# 261105902xxxx-HW-V2_1.net
KiCad netlist of a schematic drawn in EAGLE
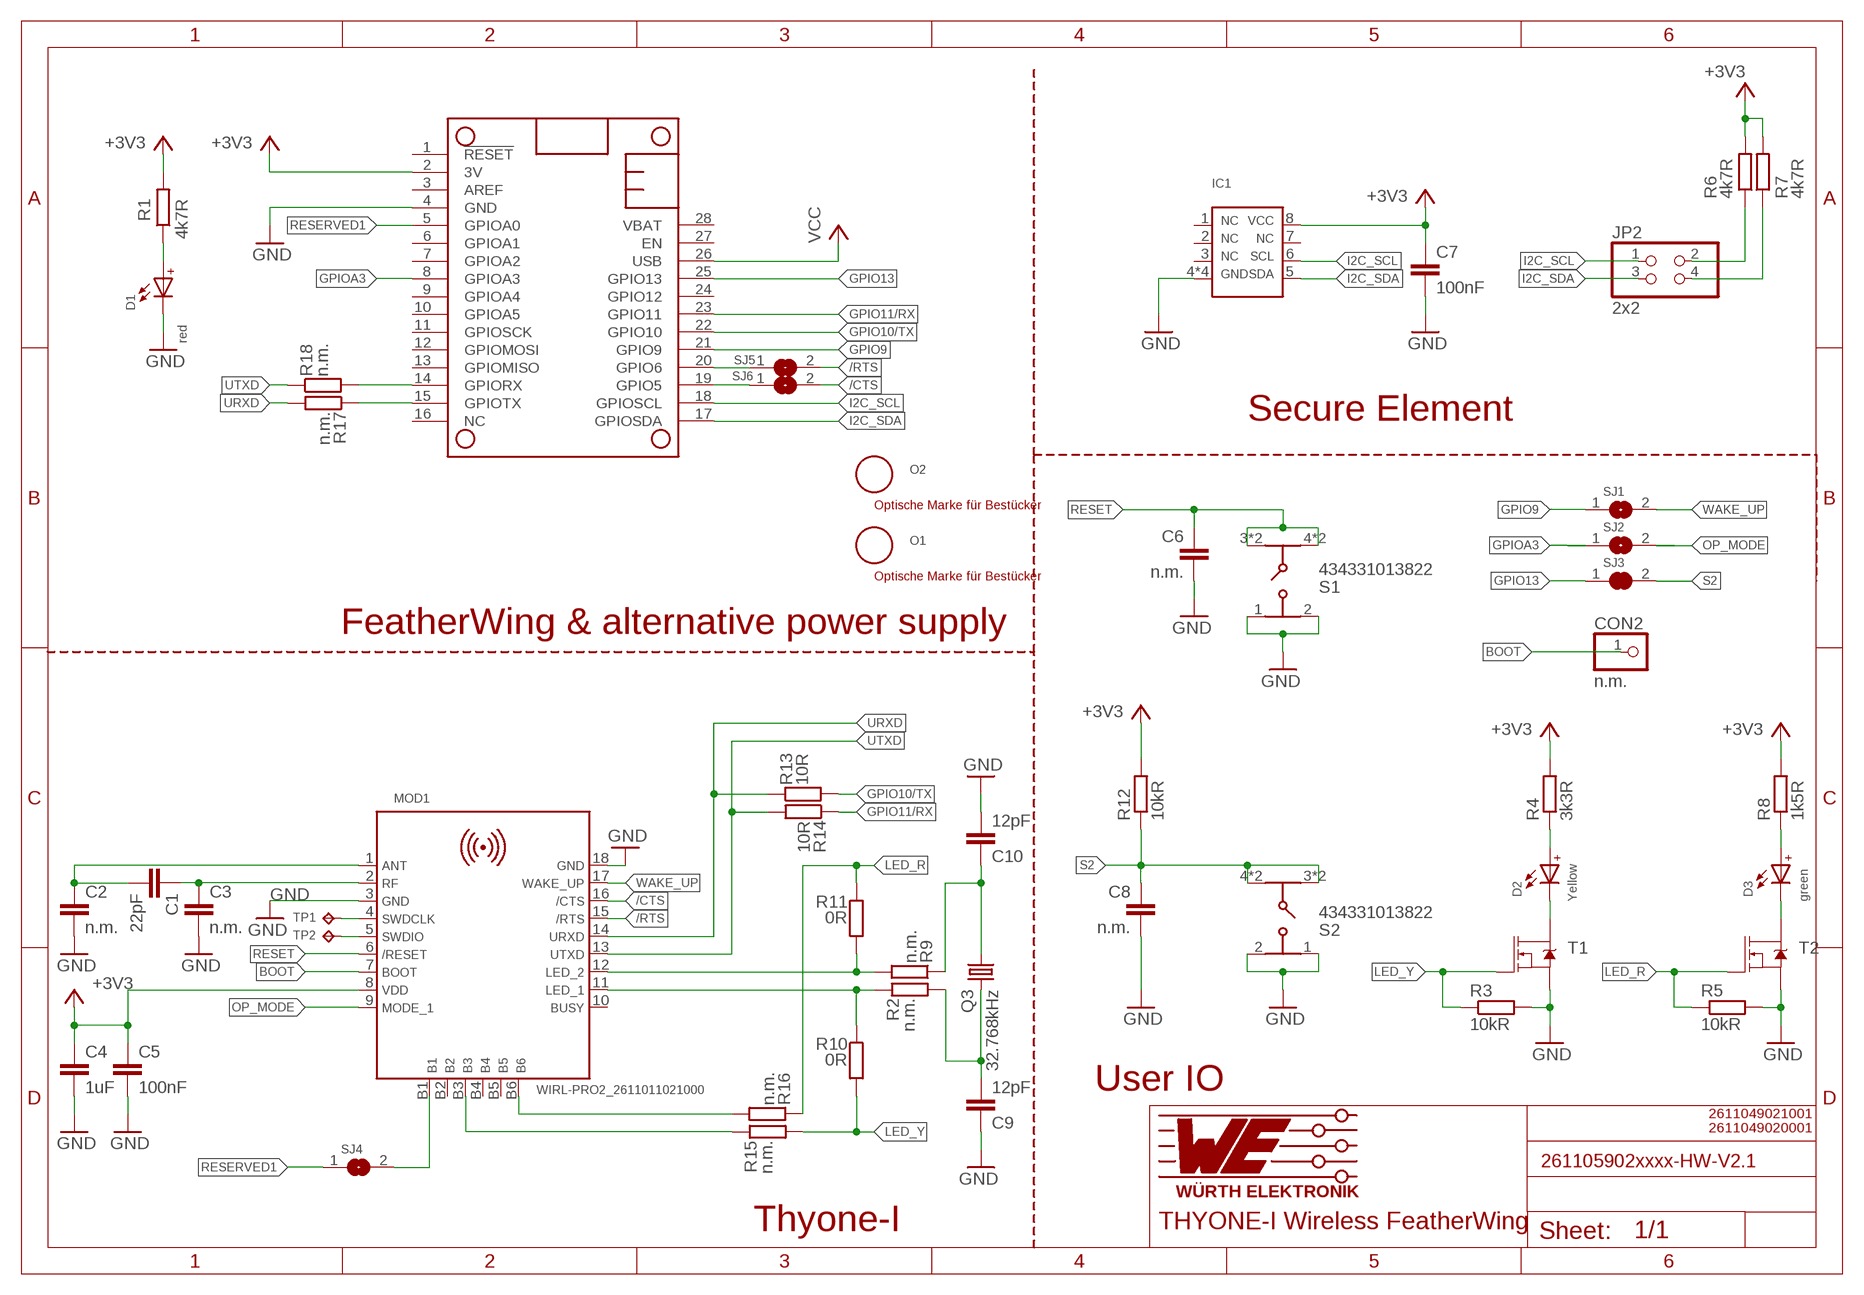
[diagram p0: schematic, sheet 1]

(export (version "E")
  (design (tool "Eeschema 10.0.6"))
  (components
    (comp (ref "C1")
      (value "22pF")
      (footprint "eagle-import:C0402_IPC")
      (fields (field (name "MANUFACTURER") "Samsung"))
      (libsource (lib "eagle-import") (part "rcl-amber_C0402_IPC22PF"))
    )
    (comp (ref "C2")
      (value "n.m.")
      (footprint "eagle-import:C0402_IPC")
      (fields (field (name "MANUFACTURER") "Würth Elektronik"))
      (libsource (lib "eagle-import") (part "C0402_IPC"))
    )
    (comp (ref "C3")
      (value "n.m.")
      (footprint "eagle-import:C0402_IPC")
      (fields (field (name "MANUFACTURER") "Würth Elektronik"))
      (libsource (lib "eagle-import") (part "C0402_IPC"))
    )
    (comp (ref "C4")
      (value "1uF")
      (footprint "eagle-import:C0402_IPC")
      (fields (field (name "MANUFACTURER") "Samsung"))
      (libsource (lib "eagle-import") (part "rcl-amber_C0402_IPC1UF"))
    )
    (comp (ref "C5")
      (value "100nF")
      (footprint "eagle-import:C0402_IPC")
      (fields (field (name "MANUFACTURER") "Yageo"))
      (libsource (lib "eagle-import") (part "rcl-amber_C0402_IPC100NF"))
    )
    (comp (ref "C6")
      (value "n.m.")
      (footprint "eagle-import:C0402_IPC")
      (fields (field (name "MANUFACTURER") "Würth Elektronik"))
      (libsource (lib "eagle-import") (part "C0402_IPC"))
    )
    (comp (ref "C7")
      (value "100nF")
      (footprint "eagle-import:C0402_IPC")
      (fields (field (name "MANUFACTURER") "Yageo"))
      (libsource (lib "eagle-import") (part "rcl-amber_C0402_IPC100NF"))
    )
    (comp (ref "C8")
      (value "n.m.")
      (footprint "eagle-import:C0402_IPC")
      (fields (field (name "MANUFACTURER") "Würth Elektronik"))
      (libsource (lib "eagle-import") (part "C0402_IPC"))
    )
    (comp (ref "C9")
      (value "12pF")
      (footprint "eagle-import:C0402_IPC")
      (fields (field (name "MANUFACTURER") "Yageo"))
      (libsource (lib "eagle-import") (part "C0402_IPC12PF"))
    )
    (comp (ref "C10")
      (value "12pF")
      (footprint "eagle-import:C0402_IPC")
      (fields (field (name "MANUFACTURER") "Yageo"))
      (libsource (lib "eagle-import") (part "C0402_IPC12PF"))
    )
    (comp (ref "CON2")
      (value "n.m.")
      (footprint "eagle-import:1X01_R")
      (libsource (lib "eagle-import") (part "PINHD-1X1/R"))
    )
    (comp (ref "D1")
      (value "red")
      (footprint "eagle-import:WL-SMSW_1204_A")
      (fields (field (name "MANUFACTURER") "Würth Elektronik"))
      (libsource (lib "eagle-import") (part "WL-SMSW_1204_155124VS73200"))
    )
    (comp (ref "D2")
      (value "Yellow")
      (footprint "eagle-import:WL-SMSW_1204_A")
      (fields (field (name "MANUFACTURER") "Würth Elektronik"))
      (libsource (lib "eagle-import") (part "WL-SMSW_1204_155124YS73200"))
    )
    (comp (ref "D3")
      (value "green")
      (footprint "eagle-import:WL-SMSW_1204_A")
      (fields (field (name "MANUFACTURER") "Würth Elektronik"))
      (libsource (lib "eagle-import") (part "WL-SMSW_1204_155124VS73200"))
    )
    (comp (ref "IC1")
      (value "ATECC608B")
      (footprint "eagle-import:UDFN-8")
      (fields (field (name "MANUFACTURER") "Microchip") (field (name "MANUFACTURER_1") "microchip"))
      (libsource (lib "eagle-import") (part "ATECC608B-TNGTLS"))
    )
    (comp (ref "JP2")
      (value "2x2")
      (footprint "eagle-import:2X02")
      (fields (field (name "MANUFACTURER") "Würth Elektronik"))
      (libsource (lib "eagle-import") (part "PINHD-2X2"))
    )
    (comp (ref "MOD1")
      (value "WIRL-PRO2_2611011021000")
      (footprint "eagle-import:WIRL-PRO2_2611011021000")
      (fields (field (name "MANUFACTURER") "Würth Elektronik"))
      (libsource (lib "eagle-import") (part "WIRL-PRO2_2611011021000"))
    )
    (comp (ref "MS1")
      (value "header: 1 x 12 & 1 x 16")
      (footprint "eagle-import:FEATHERWING")
      (fields (field (name "COMMENT") "Kit containing 2 headers") (field (name "MANUFACTURER") "Adafruit"))
      (libsource (lib "eagle-import") (part "FEATHERWING"))
    )
    (comp (ref "O1")
      (value "n.m.")
      (footprint "eagle-import:OPTISCHE_MARKE")
      (libsource (lib "eagle-import") (part "OPT_MARKE"))
    )
    (comp (ref "O2")
      (value "n.m.")
      (footprint "eagle-import:OPTISCHE_MARKE")
      (libsource (lib "eagle-import") (part "OPT_MARKE"))
    )
    (comp (ref "Q3")
      (value "32.768kHz")
      (footprint "eagle-import:3216")
      (fields
        (field (name "MANUFACTURER") "Microcrystal")
        (field (name "MANUFACTURER_1") "Würth Elektronik")
        (field (name "MANUFACTURER_2") "Microcrystal")
        (field (name "NR") "830009706")
        (field (name "NR_2") "CM7V-T1A-32.768k-9pF-20PPM-TA-QA T3")
      )
      (libsource (lib "eagle-import") (part "3216"))
    )
    (comp (ref "R1")
      (value "4k7R")
      (footprint "eagle-import:R0402_IPC")
      (fields (field (name "MANUFACTURER") "Yageo"))
      (libsource (lib "eagle-import") (part "R0402_IPC4K7"))
    )
    (comp (ref "R2")
      (value "n.m.")
      (footprint "eagle-import:R0402_IPC")
      (fields (field (name "MANUFACTURER") "Yageo"))
      (libsource (lib "eagle-import") (part "R0402_IPC"))
    )
    (comp (ref "R3")
      (value "10kR")
      (footprint "eagle-import:R0402_IPC")
      (fields (field (name "MANUFACTURER") "Yageo"))
      (libsource (lib "eagle-import") (part "R0402_IPC10KR"))
    )
    (comp (ref "R4")
      (value "3k3R")
      (footprint "eagle-import:R0402_IPC")
      (fields (field (name "MANUFACTURER") "Yageo"))
      (libsource (lib "eagle-import") (part "R0402_IPC3K3R"))
    )
    (comp (ref "R5")
      (value "10kR")
      (footprint "eagle-import:R0402_IPC")
      (fields (field (name "MANUFACTURER") "Yageo"))
      (libsource (lib "eagle-import") (part "R0402_IPC10KR"))
    )
    (comp (ref "R6")
      (value "4k7R")
      (footprint "eagle-import:R0402_IPC")
      (fields (field (name "MANUFACTURER") "Yageo"))
      (libsource (lib "eagle-import") (part "R0402_IPC4K7"))
    )
    (comp (ref "R7")
      (value "4k7R")
      (footprint "eagle-import:R0402_IPC")
      (fields (field (name "MANUFACTURER") "Yageo"))
      (libsource (lib "eagle-import") (part "R0402_IPC4K7"))
    )
    (comp (ref "R8")
      (value "1k5R")
      (footprint "eagle-import:R0402_IPC")
      (fields (field (name "MANUFACTURER") "Yageo"))
      (libsource (lib "eagle-import") (part "R0402_IPC1K5R"))
    )
    (comp (ref "R9")
      (value "n.m.")
      (footprint "eagle-import:R0402_IPC")
      (fields (field (name "MANUFACTURER") "Yageo"))
      (libsource (lib "eagle-import") (part "R0402_IPC"))
    )
    (comp (ref "R10")
      (value "0R")
      (footprint "eagle-import:R0402_IPC")
      (fields (field (name "MANUFACTURER") "Yageo"))
      (libsource (lib "eagle-import") (part "R0402_IPC0R"))
    )
    (comp (ref "R11")
      (value "0R")
      (footprint "eagle-import:R0402_IPC")
      (fields (field (name "MANUFACTURER") "Yageo"))
      (libsource (lib "eagle-import") (part "R0402_IPC0R"))
    )
    (comp (ref "R12")
      (value "10kR")
      (footprint "eagle-import:R0402_IPC")
      (fields (field (name "MANUFACTURER") "Yageo"))
      (libsource (lib "eagle-import") (part "R0402_IPC10KR"))
    )
    (comp (ref "R13")
      (value "10R")
      (footprint "eagle-import:R0402_IPC")
      (fields (field (name "MANUFACTURER") "Yageo"))
      (libsource (lib "eagle-import") (part "R0402_IPC10R"))
    )
    (comp (ref "R14")
      (value "10R")
      (footprint "eagle-import:R0402_IPC")
      (fields (field (name "MANUFACTURER") "Yageo"))
      (libsource (lib "eagle-import") (part "R0402_IPC10R"))
    )
    (comp (ref "R15")
      (value "n.m.")
      (footprint "eagle-import:R0402_IPC")
      (fields (field (name "MANUFACTURER") "Yageo"))
      (libsource (lib "eagle-import") (part "R0402_IPC"))
    )
    (comp (ref "R16")
      (value "n.m.")
      (footprint "eagle-import:R0402_IPC")
      (fields (field (name "MANUFACTURER") "Yageo"))
      (libsource (lib "eagle-import") (part "R0402_IPC"))
    )
    (comp (ref "R17")
      (value "n.m.")
      (footprint "eagle-import:R0402_IPC")
      (fields (field (name "MANUFACTURER") "Yageo"))
      (libsource (lib "eagle-import") (part "R0402_IPC"))
    )
    (comp (ref "R18")
      (value "n.m.")
      (footprint "eagle-import:R0402_IPC")
      (fields (field (name "MANUFACTURER") "Yageo"))
      (libsource (lib "eagle-import") (part "R0402_IPC"))
    )
    (comp (ref "S1")
      (value "434331013822")
      (footprint "eagle-import:434331013822")
      (fields (field (name "MANUFACTURER") "Würth Elektronik"))
      (libsource (lib "eagle-import") (part "434331013822"))
    )
    (comp (ref "S2")
      (value "434331013822")
      (footprint "eagle-import:434331013822")
      (fields (field (name "MANUFACTURER") "Würth Elektronik"))
      (libsource (lib "eagle-import") (part "434331013822"))
    )
    (comp (ref "SJ1") (value "SJ") (footprint "eagle-import:SJ") (libsource (lib "eagle-import") (part "SJ")))
    (comp (ref "SJ2") (value "SJ") (footprint "eagle-import:SJ") (libsource (lib "eagle-import") (part "SJ")))
    (comp (ref "SJ3")
      (value "SJ_SHUNTD")
      (footprint "eagle-import:SJ_D")
      (libsource (lib "eagle-import") (part "SJ_SHUNTD"))
    )
    (comp (ref "SJ4") (value "SJ") (footprint "eagle-import:SJ") (libsource (lib "eagle-import") (part "SJ")))
    (comp (ref "SJ5") (value "SJ") (footprint "eagle-import:SJ") (libsource (lib "eagle-import") (part "SJ")))
    (comp (ref "SJ6") (value "SJ") (footprint "eagle-import:SJ") (libsource (lib "eagle-import") (part "SJ")))
    (comp (ref "T1")
      (value "MOSFET-NCH-BSS138")
      (footprint "eagle-import:SOT23-3")
      (fields (field (name "COMMENT") "220mA/50V/3.5O") (field (name "MANUFACTURER") "Diodes Incorporated"))
      (libsource (lib "eagle-import") (part "MOSFET-NCH-BSS138"))
    )
    (comp (ref "T2")
      (value "MOSFET-NCH-BSS138")
      (footprint "eagle-import:SOT23-3")
      (fields (field (name "COMMENT") "220mA/50V/3.5O") (field (name "MANUFACTURER") "Diodes Incorporated"))
      (libsource (lib "eagle-import") (part "MOSFET-NCH-BSS138"))
    )
    (comp (ref "TP1")
      (value "TP15R")
      (footprint "eagle-import:TP15R")
      (libsource (lib "eagle-import") (part "TP15R"))
    )
    (comp (ref "TP2")
      (value "TP15R")
      (footprint "eagle-import:TP15R")
      (libsource (lib "eagle-import") (part "TP15R"))
    )
  )
  (nets
    (net (code "1") (name "+3V3") (class "Default")
      (node (ref "C4") (pin "1") (pinfunction "1_1") (pintype "passive"))
      (node (ref "C5") (pin "1") (pinfunction "1_1") (pintype "passive"))
      (node (ref "C7") (pin "1") (pinfunction "1_1") (pintype "passive"))
      (node (ref "IC1") (pin "8") (pinfunction "VCC_8") (pintype "power_in"))
      (node (ref "MOD1") (pin "8") (pinfunction "VDD_8") (pintype "bidirectional"))
      (node (ref "MS1") (pin "2") (pinfunction "3V_2") (pintype "power_in"))
      (node (ref "R1") (pin "2") (pinfunction "2_2") (pintype "passive"))
      (node (ref "R12") (pin "2") (pinfunction "2_2") (pintype "passive"))
      (node (ref "R4") (pin "2") (pinfunction "2_2") (pintype "passive"))
      (node (ref "R6") (pin "2") (pinfunction "2_2") (pintype "passive"))
      (node (ref "R7") (pin "2") (pinfunction "2_2") (pintype "passive"))
      (node (ref "R8") (pin "2") (pinfunction "2_2") (pintype "passive"))
    )
    (net (code "2") (name "/VBAT") (class "Default")
      (node (ref "MS1") (pin "28") (pinfunction "VBAT_28") (pintype "power_in"))
    )
    (net (code "3") (name "BOOT") (class "Default")
      (node (ref "CON2") (pin "1") (pinfunction "1_1") (pintype "passive"))
      (node (ref "MOD1") (pin "7") (pinfunction "P0.02/BOOT_7") (pintype "bidirectional"))
    )
    (net (code "4") (name "GND") (class "Default")
      (node (ref "C10") (pin "2") (pinfunction "2_2") (pintype "passive"))
      (node (ref "C2") (pin "2") (pinfunction "2_2") (pintype "passive"))
      (node (ref "C3") (pin "2") (pinfunction "2_2") (pintype "passive"))
      (node (ref "C4") (pin "2") (pinfunction "2_2") (pintype "passive"))
      (node (ref "C5") (pin "2") (pinfunction "2_2") (pintype "passive"))
      (node (ref "C6") (pin "2") (pinfunction "2_2") (pintype "passive"))
      (node (ref "C7") (pin "2") (pinfunction "2_2") (pintype "passive"))
      (node (ref "C8") (pin "2") (pinfunction "2_2") (pintype "passive"))
      (node (ref "C9") (pin "1") (pinfunction "1_1") (pintype "passive"))
      (node (ref "D1") (pin "1") (pinfunction "-_1") (pintype "passive"))
      (node (ref "IC1") (pin "4") (pinfunction "GND_4") (pintype "power_in"))
      (node (ref "IC1") (pin "P$1") (pinfunction "GND_P$1") (pintype "power_in"))
      (node (ref "IC1") (pin "P$2") (pinfunction "GND_P$2") (pintype "power_in"))
      (node (ref "IC1") (pin "THERMAL_PAD") (pinfunction "GND_THERMAL_PAD") (pintype "power_in"))
      (node (ref "MOD1") (pin "18") (pinfunction "GND_18") (pintype "bidirectional"))
      (node (ref "MOD1") (pin "3") (pinfunction "GND_3") (pintype "bidirectional"))
      (node (ref "MS1") (pin "4") (pinfunction "GND_4") (pintype "power_in"))
      (node (ref "R3") (pin "2") (pinfunction "2_2") (pintype "passive"))
      (node (ref "R5") (pin "2") (pinfunction "2_2") (pintype "passive"))
      (node (ref "S1") (pin "1") (pinfunction "1_1") (pintype "passive"))
      (node (ref "S1") (pin "2") (pinfunction "2_2") (pintype "passive"))
      (node (ref "S2") (pin "1") (pinfunction "1_1") (pintype "passive"))
      (node (ref "S2") (pin "2") (pinfunction "2_2") (pintype "passive"))
      (node (ref "T1") (pin "2") (pinfunction "S_2") (pintype "bidirectional"))
      (node (ref "T2") (pin "2") (pinfunction "S_2") (pintype "bidirectional"))
    )
    (net (code "5") (name "GPIO9") (class "Default")
      (node (ref "MS1") (pin "21") (pinfunction "GPIO9_21") (pintype "bidirectional"))
      (node (ref "SJ1") (pin "1") (pinfunction "1_1") (pintype "passive"))
    )
    (net (code "6") (name "GPIO10{slash}TX") (class "Default")
      (node (ref "MS1") (pin "22") (pinfunction "GPIO10_22") (pintype "bidirectional"))
      (node (ref "R13") (pin "2") (pinfunction "2_2") (pintype "passive"))
    )
    (net (code "7") (name "GPIO11{slash}RX") (class "Default")
      (node (ref "MS1") (pin "23") (pinfunction "GPIO11_23") (pintype "bidirectional"))
      (node (ref "R14") (pin "1") (pinfunction "1_1") (pintype "passive"))
    )
    (net (code "8") (name "GPIO13") (class "Default")
      (node (ref "MS1") (pin "25") (pinfunction "GPIO13_25") (pintype "bidirectional"))
      (node (ref "SJ3") (pin "1") (pinfunction "1_1") (pintype "passive"))
    )
    (net (code "9") (name "GPIOA3") (class "Default")
      (node (ref "MS1") (pin "8") (pinfunction "GPIOA3_8") (pintype "bidirectional"))
      (node (ref "SJ2") (pin "1") (pinfunction "1_1") (pintype "passive"))
    )
    (net (code "10") (name "I2C_SCL") (class "Default")
      (node (ref "IC1") (pin "6") (pinfunction "SCL_6") (pintype "bidirectional"))
      (node (ref "JP2") (pin "1") (pinfunction "1_1") (pintype "passive"))
      (node (ref "MS1") (pin "18") (pinfunction "GPIOSCL_18") (pintype "bidirectional"))
    )
    (net (code "11") (name "I2C_SDA") (class "Default")
      (node (ref "IC1") (pin "5") (pinfunction "SDA_5") (pintype "bidirectional"))
      (node (ref "JP2") (pin "3") (pinfunction "3_3") (pintype "passive"))
      (node (ref "MS1") (pin "17") (pinfunction "GPIOSDA_17") (pintype "bidirectional"))
    )
    (net (code "12") (name "LED_R") (class "Default")
      (node (ref "R11") (pin "1") (pinfunction "1_1") (pintype "passive"))
      (node (ref "R16") (pin "1") (pinfunction "1_1") (pintype "passive"))
      (node (ref "R5") (pin "1") (pinfunction "1_1") (pintype "passive"))
      (node (ref "T2") (pin "1") (pinfunction "G_1") (pintype "bidirectional"))
    )
    (net (code "13") (name "LED_Y") (class "Default")
      (node (ref "R10") (pin "2") (pinfunction "2_2") (pintype "passive"))
      (node (ref "R15") (pin "2") (pinfunction "2_2") (pintype "passive"))
      (node (ref "R3") (pin "1") (pinfunction "1_1") (pintype "passive"))
      (node (ref "T1") (pin "1") (pinfunction "G_1") (pintype "bidirectional"))
    )
    (net (code "14") (name "Net-(C9-Pad2)") (class "Default")
      (node (ref "C9") (pin "2") (pinfunction "2_2") (pintype "passive"))
      (node (ref "Q3") (pin "2") (pinfunction "2_2") (pintype "passive"))
      (node (ref "R2") (pin "2") (pinfunction "2_2") (pintype "passive"))
    )
    (net (code "15") (name "Net-(C10-Pad1)") (class "Default")
      (node (ref "C10") (pin "1") (pinfunction "1_1") (pintype "passive"))
      (node (ref "Q3") (pin "1") (pinfunction "1_1") (pintype "passive"))
      (node (ref "R9") (pin "1") (pinfunction "1_1") (pintype "passive"))
    )
    (net (code "16") (name "Net-(D1-+)") (class "Default")
      (node (ref "D1") (pin "2") (pinfunction "+_2") (pintype "passive"))
      (node (ref "R1") (pin "1") (pinfunction "1_1") (pintype "passive"))
    )
    (net (code "17") (name "Net-(D2-+)") (class "Default")
      (node (ref "D2") (pin "2") (pinfunction "+_2") (pintype "passive"))
      (node (ref "R4") (pin "1") (pinfunction "1_1") (pintype "passive"))
    )
    (net (code "18") (name "Net-(D2--)") (class "Default")
      (node (ref "D2") (pin "1") (pinfunction "-_1") (pintype "passive"))
      (node (ref "T1") (pin "3") (pinfunction "D_3") (pintype "bidirectional"))
    )
    (net (code "19") (name "Net-(D3-+)") (class "Default")
      (node (ref "D3") (pin "2") (pinfunction "+_2") (pintype "passive"))
      (node (ref "R8") (pin "1") (pinfunction "1_1") (pintype "passive"))
    )
    (net (code "20") (name "Net-(D3--)") (class "Default")
      (node (ref "D3") (pin "1") (pinfunction "-_1") (pintype "passive"))
      (node (ref "T2") (pin "3") (pinfunction "D_3") (pintype "bidirectional"))
    )
    (net (code "21") (name "Net-(JP2-Pad2)") (class "Default")
      (node (ref "JP2") (pin "2") (pinfunction "2_2") (pintype "passive"))
      (node (ref "R6") (pin "1") (pinfunction "1_1") (pintype "passive"))
    )
    (net (code "22") (name "Net-(JP2-Pad4)") (class "Default")
      (node (ref "JP2") (pin "4") (pinfunction "4_4") (pintype "passive"))
      (node (ref "R7") (pin "1") (pinfunction "1_1") (pintype "passive"))
    )
    (net (code "23") (name "Net-(MOD1-ANT_PAD)") (class "Default")
      (node (ref "C1") (pin "2") (pinfunction "2_2") (pintype "passive"))
      (node (ref "C2") (pin "1") (pinfunction "1_1") (pintype "passive"))
      (node (ref "MOD1") (pin "1") (pinfunction "ANT_PAD_1") (pintype "bidirectional"))
    )
    (net (code "24") (name "Net-(MOD1-P0.00{slash}LED_1)") (class "Default")
      (node (ref "MOD1") (pin "11") (pinfunction "P0.00/LED_1_11") (pintype "bidirectional"))
      (node (ref "R10") (pin "1") (pinfunction "1_1") (pintype "passive"))
      (node (ref "R2") (pin "1") (pinfunction "1_1") (pintype "passive"))
    )
    (net (code "25") (name "Net-(MOD1-P0.01{slash}LED_2)") (class "Default")
      (node (ref "MOD1") (pin "12") (pinfunction "P0.01/LED_2_12") (pintype "bidirectional"))
      (node (ref "R11") (pin "2") (pinfunction "2_2") (pintype "passive"))
      (node (ref "R9") (pin "2") (pinfunction "2_2") (pintype "passive"))
    )
    (net (code "26") (name "Net-(MOD1-PadB1)") (class "Default")
      (node (ref "MOD1") (pin "B1") (pinfunction "B1_B1") (pintype "bidirectional"))
      (node (ref "SJ4") (pin "2") (pinfunction "2_2") (pintype "passive"))
    )
    (net (code "27") (name "Net-(MOD1-PadB3)") (class "Default")
      (node (ref "MOD1") (pin "B3") (pinfunction "B3_B3") (pintype "bidirectional"))
      (node (ref "R15") (pin "1") (pinfunction "1_1") (pintype "passive"))
    )
    (net (code "28") (name "Net-(MOD1-PadB6)") (class "Default")
      (node (ref "MOD1") (pin "B6") (pinfunction "B6_B6") (pintype "bidirectional"))
      (node (ref "R16") (pin "2") (pinfunction "2_2") (pintype "passive"))
    )
    (net (code "29") (name "Net-(MOD1-RF)") (class "Default")
      (node (ref "C1") (pin "1") (pinfunction "1_1") (pintype "passive"))
      (node (ref "C3") (pin "1") (pinfunction "1_1") (pintype "passive"))
      (node (ref "MOD1") (pin "2") (pinfunction "RF_2") (pintype "bidirectional"))
    )
    (net (code "30") (name "Net-(MOD1-SWDCLK)") (class "Default")
      (node (ref "MOD1") (pin "4") (pinfunction "SWDCLK_4") (pintype "bidirectional"))
      (node (ref "TP1") (pin "P$1") (pinfunction "TP_P$1") (pintype "passive"))
    )
    (net (code "31") (name "Net-(MOD1-SWDIO)") (class "Default")
      (node (ref "MOD1") (pin "5") (pinfunction "SWDIO_5") (pintype "bidirectional"))
      (node (ref "TP2") (pin "P$1") (pinfunction "TP_P$1") (pintype "passive"))
    )
    (net (code "32") (name "Net-(MS1-GPIO5)") (class "Default")
      (node (ref "MS1") (pin "19") (pinfunction "GPIO5_19") (pintype "bidirectional"))
      (node (ref "SJ6") (pin "1") (pinfunction "1_1") (pintype "passive"))
    )
    (net (code "33") (name "Net-(MS1-GPIO6)") (class "Default")
      (node (ref "MS1") (pin "20") (pinfunction "GPIO6_20") (pintype "bidirectional"))
      (node (ref "SJ5") (pin "1") (pinfunction "1_1") (pintype "passive"))
    )
    (net (code "34") (name "Net-(MS1-GPIORX)") (class "Default")
      (node (ref "MS1") (pin "14") (pinfunction "GPIORX_14") (pintype "bidirectional"))
      (node (ref "R18") (pin "2") (pinfunction "2_2") (pintype "passive"))
    )
    (net (code "35") (name "Net-(MS1-GPIOTX)") (class "Default")
      (node (ref "MS1") (pin "15") (pinfunction "GPIOTX_15") (pintype "bidirectional"))
      (node (ref "R17") (pin "1") (pinfunction "1_1") (pintype "passive"))
    )
    (net (code "36") (name "OP_MODE") (class "Default")
      (node (ref "MOD1") (pin "9") (pinfunction "P0.19/MODE_1_9") (pintype "bidirectional"))
      (node (ref "SJ2") (pin "2") (pinfunction "2_2") (pintype "passive"))
    )
    (net (code "37") (name "RESERVED1") (class "Default")
      (node (ref "MS1") (pin "5") (pinfunction "GPIOA0_5") (pintype "bidirectional"))
      (node (ref "SJ4") (pin "1") (pinfunction "1_1") (pintype "passive"))
    )
    (net (code "38") (name "RESET") (class "Default")
      (node (ref "C6") (pin "1") (pinfunction "1_1") (pintype "passive"))
      (node (ref "MOD1") (pin "6") (pinfunction "P0.18/RESET_6") (pintype "bidirectional"))
      (node (ref "S1") (pin "3") (pinfunction "3_3") (pintype "passive"))
      (node (ref "S1") (pin "4") (pinfunction "4_4") (pintype "passive"))
      (node (ref "S1") (pin "5") (pinfunction "3_5") (pintype "passive"))
      (node (ref "S1") (pin "6") (pinfunction "4_6") (pintype "passive"))
    )
    (net (code "39") (name "S2") (class "Default")
      (node (ref "C8") (pin "1") (pinfunction "1_1") (pintype "passive"))
      (node (ref "R12") (pin "1") (pinfunction "1_1") (pintype "passive"))
      (node (ref "S2") (pin "3") (pinfunction "3_3") (pintype "passive"))
      (node (ref "S2") (pin "4") (pinfunction "4_4") (pintype "passive"))
      (node (ref "S2") (pin "5") (pinfunction "3_5") (pintype "passive"))
      (node (ref "S2") (pin "6") (pinfunction "4_6") (pintype "passive"))
      (node (ref "SJ3") (pin "2") (pinfunction "2_2") (pintype "passive"))
    )
    (net (code "40") (name "URXD") (class "Default")
      (node (ref "MOD1") (pin "14") (pinfunction "P1.09/URXD_14") (pintype "bidirectional"))
      (node (ref "R13") (pin "1") (pinfunction "1_1") (pintype "passive"))
      (node (ref "R17") (pin "2") (pinfunction "2_2") (pintype "passive"))
    )
    (net (code "41") (name "UTXD") (class "Default")
      (node (ref "MOD1") (pin "13") (pinfunction "P1.08/UTXD_13") (pintype "bidirectional"))
      (node (ref "R14") (pin "2") (pinfunction "2_2") (pintype "passive"))
      (node (ref "R18") (pin "1") (pinfunction "1_1") (pintype "passive"))
    )
    (net (code "42") (name "VCC") (class "Default")
      (node (ref "MS1") (pin "26") (pinfunction "USB_26") (pintype "power_in"))
    )
    (net (code "43") (name "WAKE_UP") (class "Default")
      (node (ref "MOD1") (pin "17") (pinfunction "P0.03/WAKE_UP_17") (pintype "bidirectional"))
      (node (ref "SJ1") (pin "2") (pinfunction "2_2") (pintype "passive"))
    )
    (net (code "44") (name "unconnected-(IC1-NC1-Pad1)") (class "Default")
      (node (ref "IC1") (pin "1") (pinfunction "NC1_1") (pintype "no_connect"))
    )
    (net (code "45") (name "unconnected-(IC1-NC2-Pad2)") (class "Default")
      (node (ref "IC1") (pin "2") (pinfunction "NC2_2") (pintype "no_connect"))
    )
    (net (code "46") (name "unconnected-(IC1-NC3-Pad3)") (class "Default")
      (node (ref "IC1") (pin "3") (pinfunction "NC3_3") (pintype "no_connect"))
    )
    (net (code "47") (name "unconnected-(IC1-NC4-Pad7)") (class "Default")
      (node (ref "IC1") (pin "7") (pinfunction "NC4_7") (pintype "no_connect"))
    )
    (net (code "48") (name "unconnected-(MOD1-P0.22{slash}BUSY-Pad10)") (class "Default")
      (node (ref "MOD1") (pin "10") (pinfunction "P0.22/BUSY_10") (pintype "bidirectional"))
    )
    (net (code "49") (name "unconnected-(MOD1-PadB2)") (class "Default")
      (node (ref "MOD1") (pin "B2") (pinfunction "B2_B2") (pintype "bidirectional"))
    )
    (net (code "50") (name "unconnected-(MOD1-PadB4)") (class "Default")
      (node (ref "MOD1") (pin "B4") (pinfunction "B4_B4") (pintype "bidirectional"))
    )
    (net (code "51") (name "unconnected-(MOD1-PadB5)") (class "Default")
      (node (ref "MOD1") (pin "B5") (pinfunction "B5_B5") (pintype "bidirectional"))
    )
    (net (code "52") (name "unconnected-(MS1-AREF-Pad3)") (class "Default")
      (node (ref "MS1") (pin "3") (pinfunction "AREF_3") (pintype "passive"))
    )
    (net (code "53") (name "unconnected-(MS1-EN-Pad27)") (class "Default")
      (node (ref "MS1") (pin "27") (pinfunction "EN_27") (pintype "passive"))
    )
    (net (code "54") (name "unconnected-(MS1-GPIO12-Pad24)") (class "Default")
      (node (ref "MS1") (pin "24") (pinfunction "GPIO12_24") (pintype "bidirectional"))
    )
    (net (code "55") (name "unconnected-(MS1-GPIOA1-Pad6)") (class "Default")
      (node (ref "MS1") (pin "6") (pinfunction "GPIOA1_6") (pintype "bidirectional"))
    )
    (net (code "56") (name "unconnected-(MS1-GPIOA2-Pad7)") (class "Default")
      (node (ref "MS1") (pin "7") (pinfunction "GPIOA2_7") (pintype "bidirectional"))
    )
    (net (code "57") (name "unconnected-(MS1-GPIOA4-Pad9)") (class "Default")
      (node (ref "MS1") (pin "9") (pinfunction "GPIOA4_9") (pintype "bidirectional"))
    )
    (net (code "58") (name "unconnected-(MS1-GPIOA5-Pad10)") (class "Default")
      (node (ref "MS1") (pin "10") (pinfunction "GPIOA5_10") (pintype "bidirectional"))
    )
    (net (code "59") (name "unconnected-(MS1-GPIOMISO-Pad13)") (class "Default")
      (node (ref "MS1") (pin "13") (pinfunction "GPIOMISO_13") (pintype "bidirectional"))
    )
    (net (code "60") (name "unconnected-(MS1-GPIOMOSI-Pad12)") (class "Default")
      (node (ref "MS1") (pin "12") (pinfunction "GPIOMOSI_12") (pintype "bidirectional"))
    )
    (net (code "61") (name "unconnected-(MS1-GPIOSCK-Pad11)") (class "Default")
      (node (ref "MS1") (pin "11") (pinfunction "GPIOSCK_11") (pintype "bidirectional"))
    )
    (net (code "62") (name "unconnected-(MS1-NC-Pad16)") (class "Default")
      (node (ref "MS1") (pin "16") (pinfunction "NC_16") (pintype "passive"))
    )
    (net (code "63") (name "unconnected-(MS1-~{RESET}-Pad1)") (class "Default")
      (node (ref "MS1") (pin "1") (pinfunction "~{RESET}_1") (pintype "input"))
    )
    (net (code "64") (name "{slash}CTS") (class "Default")
      (node (ref "MOD1") (pin "16") (pinfunction "P0.12/~{CTS}_16") (pintype "bidirectional"))
      (node (ref "SJ6") (pin "2") (pinfunction "2_2") (pintype "passive"))
    )
    (net (code "65") (name "{slash}RTS") (class "Default")
      (node (ref "MOD1") (pin "15") (pinfunction "P0.11/~{RTS}_15") (pintype "bidirectional"))
      (node (ref "SJ5") (pin "2") (pinfunction "2_2") (pintype "passive"))
    )
  )
)
